# temperature_2.net
KiCad netlist of a schematic drawn in EAGLE
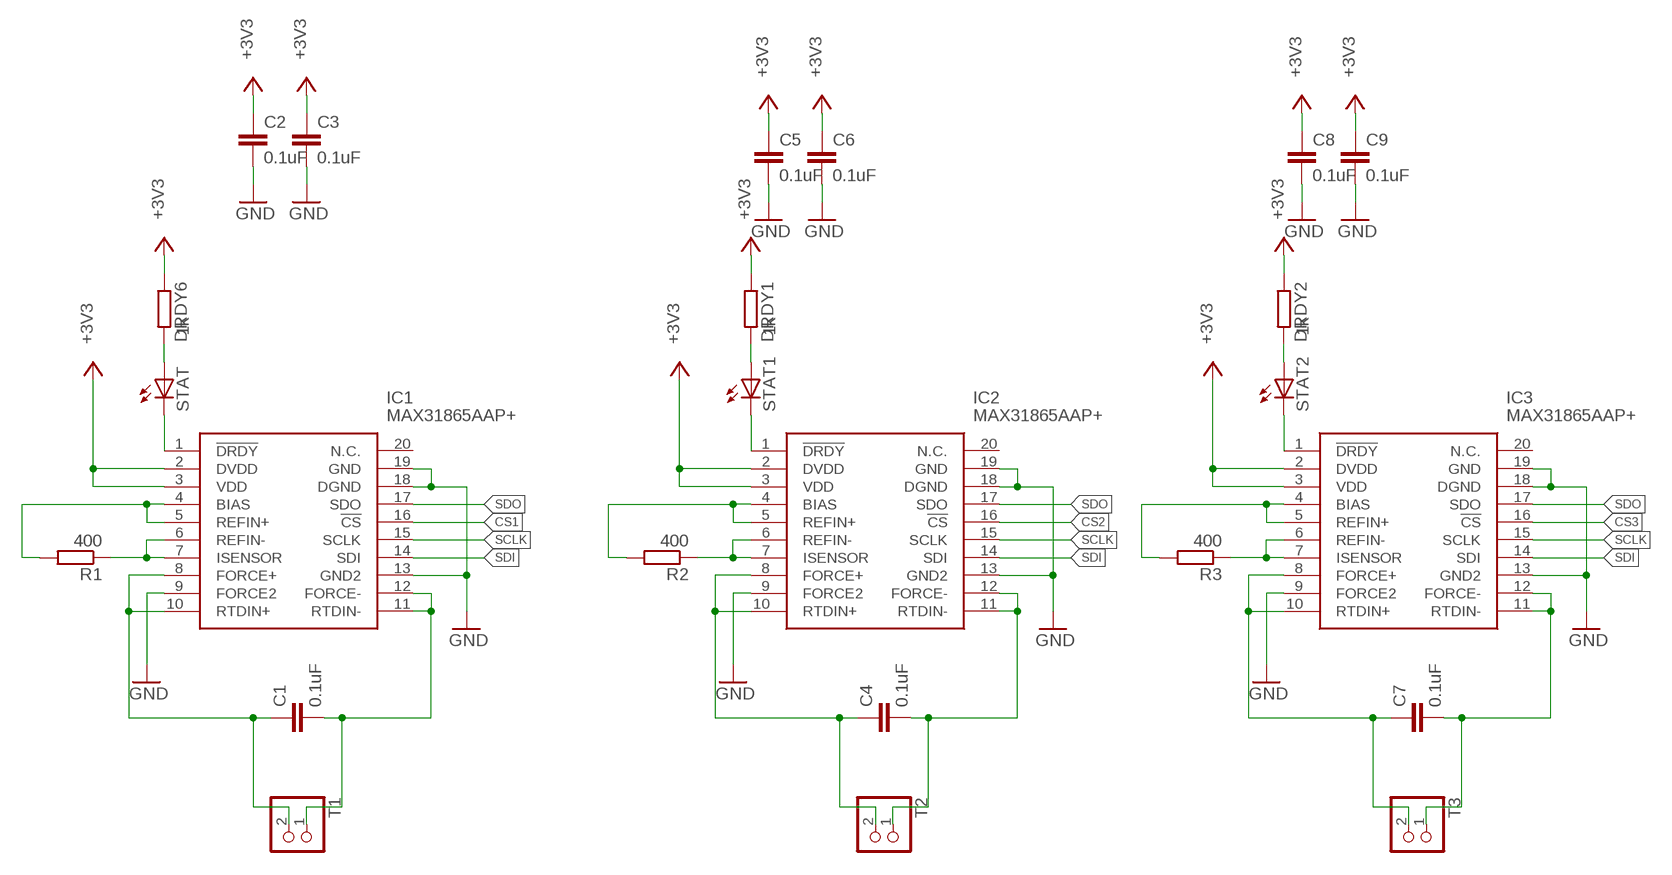
[diagram p0: schematic, sheet 1, part 1 of 2]
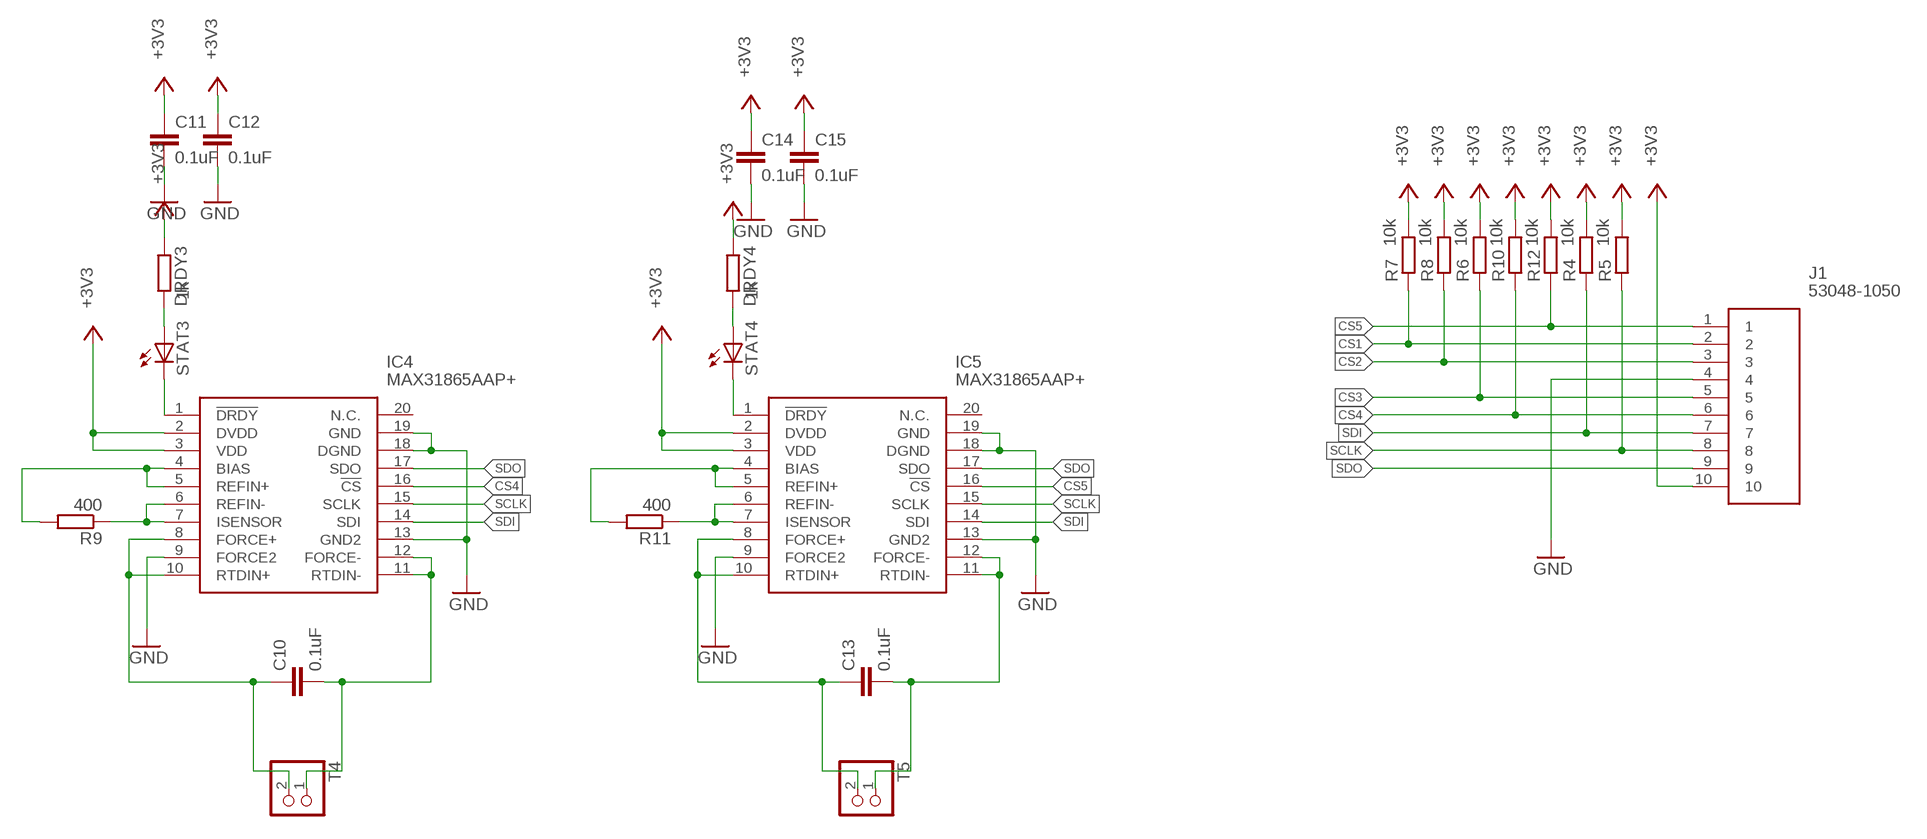
[diagram p1: schematic, sheet 1, part 2 of 2]

(export (version "E")
  (design (tool "Eeschema 10.0.6"))
  (components
    (comp (ref "C1")
      (value "0.1uF")
      (footprint "eagle-import:C0603K")
      (libsource (lib "eagle-import") (part "C-EUC0603K"))
    )
    (comp (ref "C2")
      (value "0.1uF")
      (footprint "eagle-import:C0603K")
      (libsource (lib "eagle-import") (part "C-EUC0603K"))
    )
    (comp (ref "C3")
      (value "0.1uF")
      (footprint "eagle-import:C0603K")
      (libsource (lib "eagle-import") (part "C-EUC0603K"))
    )
    (comp (ref "C4")
      (value "0.1uF")
      (footprint "eagle-import:C0603K")
      (libsource (lib "eagle-import") (part "C-EUC0603K"))
    )
    (comp (ref "C5")
      (value "0.1uF")
      (footprint "eagle-import:C0603K")
      (libsource (lib "eagle-import") (part "C-EUC0603K"))
    )
    (comp (ref "C6")
      (value "0.1uF")
      (footprint "eagle-import:C0603K")
      (libsource (lib "eagle-import") (part "C-EUC0603K"))
    )
    (comp (ref "C7")
      (value "0.1uF")
      (footprint "eagle-import:C0603K")
      (libsource (lib "eagle-import") (part "C-EUC0603K"))
    )
    (comp (ref "C8")
      (value "0.1uF")
      (footprint "eagle-import:C0603K")
      (libsource (lib "eagle-import") (part "C-EUC0603K"))
    )
    (comp (ref "C9")
      (value "0.1uF")
      (footprint "eagle-import:C0603K")
      (libsource (lib "eagle-import") (part "C-EUC0603K"))
    )
    (comp (ref "C10")
      (value "0.1uF")
      (footprint "eagle-import:C0603K")
      (libsource (lib "eagle-import") (part "C-EUC0603K"))
    )
    (comp (ref "C11")
      (value "0.1uF")
      (footprint "eagle-import:C0603K")
      (libsource (lib "eagle-import") (part "C-EUC0603K"))
    )
    (comp (ref "C12")
      (value "0.1uF")
      (footprint "eagle-import:C0603K")
      (libsource (lib "eagle-import") (part "C-EUC0603K"))
    )
    (comp (ref "C13")
      (value "0.1uF")
      (footprint "eagle-import:C0603K")
      (libsource (lib "eagle-import") (part "C-EUC0603K"))
    )
    (comp (ref "C14")
      (value "0.1uF")
      (footprint "eagle-import:C0603K")
      (libsource (lib "eagle-import") (part "C-EUC0603K"))
    )
    (comp (ref "C15")
      (value "0.1uF")
      (footprint "eagle-import:C0603K")
      (libsource (lib "eagle-import") (part "C-EUC0603K"))
    )
    (comp (ref "DRDY1")
      (value "1k")
      (footprint "eagle-import:R0603")
      (libsource (lib "eagle-import") (part "R-EU_R0603"))
    )
    (comp (ref "DRDY2")
      (value "1k")
      (footprint "eagle-import:R0603")
      (libsource (lib "eagle-import") (part "R-EU_R0603"))
    )
    (comp (ref "DRDY3")
      (value "1k")
      (footprint "eagle-import:R0603")
      (libsource (lib "eagle-import") (part "R-EU_R0603"))
    )
    (comp (ref "DRDY4")
      (value "1k")
      (footprint "eagle-import:R0603")
      (libsource (lib "eagle-import") (part "R-EU_R0603"))
    )
    (comp (ref "DRDY6")
      (value "1k")
      (footprint "eagle-import:R0603")
      (libsource (lib "eagle-import") (part "R-EU_R0603"))
    )
    (comp (ref "IC1")
      (value "MAX31865AAP+")
      (footprint "eagle-import:SOP65P778X199-20N")
      (fields
        (field (name "MOUSER_PART_NUMBER") "700-MAX31865AAP+")
        (field (name "RS_PART_NUMBER") "1901435")
      )
      (libsource (lib "eagle-import") (part "MAX31865AAP+"))
    )
    (comp (ref "IC2")
      (value "MAX31865AAP+")
      (footprint "eagle-import:SOP65P778X199-20N")
      (fields
        (field (name "MOUSER_PART_NUMBER") "700-MAX31865AAP+")
        (field (name "RS_PART_NUMBER") "1901435")
      )
      (libsource (lib "eagle-import") (part "MAX31865AAP+"))
    )
    (comp (ref "IC3")
      (value "MAX31865AAP+")
      (footprint "eagle-import:SOP65P778X199-20N")
      (fields
        (field (name "MOUSER_PART_NUMBER") "700-MAX31865AAP+")
        (field (name "RS_PART_NUMBER") "1901435")
      )
      (libsource (lib "eagle-import") (part "MAX31865AAP+"))
    )
    (comp (ref "IC4")
      (value "MAX31865AAP+")
      (footprint "eagle-import:SOP65P778X199-20N")
      (fields
        (field (name "MOUSER_PART_NUMBER") "700-MAX31865AAP+")
        (field (name "RS_PART_NUMBER") "1901435")
      )
      (libsource (lib "eagle-import") (part "MAX31865AAP+"))
    )
    (comp (ref "IC5")
      (value "MAX31865AAP+")
      (footprint "eagle-import:SOP65P778X199-20N")
      (fields
        (field (name "MOUSER_PART_NUMBER") "700-MAX31865AAP+")
        (field (name "RS_PART_NUMBER") "1901435")
      )
      (libsource (lib "eagle-import") (part "MAX31865AAP+"))
    )
    (comp (ref "J1")
      (value "53048-1050")
      (footprint "eagle-import:SHDRRA10W25P0X125_1X10_1425X55")
      (fields (field (name "MOUSER_PART_NUMBER") "538-53048-1050"))
      (libsource (lib "eagle-import") (part "53048-1050"))
    )
    (comp (ref "R1")
      (value "400")
      (footprint "eagle-import:R1206")
      (libsource (lib "eagle-import") (part "R-EU_R1206"))
    )
    (comp (ref "R2")
      (value "400")
      (footprint "eagle-import:R1206")
      (libsource (lib "eagle-import") (part "R-EU_R1206"))
    )
    (comp (ref "R3")
      (value "400")
      (footprint "eagle-import:R1206")
      (libsource (lib "eagle-import") (part "R-EU_R1206"))
    )
    (comp (ref "R4")
      (value "10k")
      (footprint "eagle-import:R0603")
      (libsource (lib "eagle-import") (part "R-EU_R0603"))
    )
    (comp (ref "R5")
      (value "10k")
      (footprint "eagle-import:R0603")
      (libsource (lib "eagle-import") (part "R-EU_R0603"))
    )
    (comp (ref "R6")
      (value "10k")
      (footprint "eagle-import:R0603")
      (libsource (lib "eagle-import") (part "R-EU_R0603"))
    )
    (comp (ref "R7")
      (value "10k")
      (footprint "eagle-import:R0603")
      (libsource (lib "eagle-import") (part "R-EU_R0603"))
    )
    (comp (ref "R8")
      (value "10k")
      (footprint "eagle-import:R0603")
      (libsource (lib "eagle-import") (part "R-EU_R0603"))
    )
    (comp (ref "R9")
      (value "400")
      (footprint "eagle-import:R1206")
      (libsource (lib "eagle-import") (part "R-EU_R1206"))
    )
    (comp (ref "R10")
      (value "10k")
      (footprint "eagle-import:R0603")
      (libsource (lib "eagle-import") (part "R-EU_R0603"))
    )
    (comp (ref "R11")
      (value "400")
      (footprint "eagle-import:R1206")
      (libsource (lib "eagle-import") (part "R-EU_R1206"))
    )
    (comp (ref "R12")
      (value "10k")
      (footprint "eagle-import:R0603")
      (libsource (lib "eagle-import") (part "R-EU_R0603"))
    )
    (comp (ref "STAT")
      (value "LEDCHIPLED_0805")
      (footprint "eagle-import:CHIPLED_0805")
      (libsource (lib "eagle-import") (part "LEDCHIPLED_0805"))
    )
    (comp (ref "STAT1")
      (value "LEDCHIPLED_0805")
      (footprint "eagle-import:CHIPLED_0805")
      (libsource (lib "eagle-import") (part "LEDCHIPLED_0805"))
    )
    (comp (ref "STAT2")
      (value "LEDCHIPLED_0805")
      (footprint "eagle-import:CHIPLED_0805")
      (libsource (lib "eagle-import") (part "LEDCHIPLED_0805"))
    )
    (comp (ref "STAT3")
      (value "LEDCHIPLED_0805")
      (footprint "eagle-import:CHIPLED_0805")
      (libsource (lib "eagle-import") (part "LEDCHIPLED_0805"))
    )
    (comp (ref "STAT4")
      (value "LEDCHIPLED_0805")
      (footprint "eagle-import:CHIPLED_0805")
      (libsource (lib "eagle-import") (part "LEDCHIPLED_0805"))
    )
    (comp (ref "T1")
      (value "PINHD-1X2")
      (footprint "eagle-import:1X02")
      (libsource (lib "eagle-import") (part "PINHD-1X2"))
    )
    (comp (ref "T2")
      (value "PINHD-1X2")
      (footprint "eagle-import:1X02")
      (libsource (lib "eagle-import") (part "PINHD-1X2"))
    )
    (comp (ref "T3")
      (value "PINHD-1X2")
      (footprint "eagle-import:1X02")
      (libsource (lib "eagle-import") (part "PINHD-1X2"))
    )
    (comp (ref "T4")
      (value "PINHD-1X2")
      (footprint "eagle-import:1X02")
      (libsource (lib "eagle-import") (part "PINHD-1X2"))
    )
    (comp (ref "T5")
      (value "PINHD-1X2")
      (footprint "eagle-import:1X02")
      (libsource (lib "eagle-import") (part "PINHD-1X2"))
    )
  )
  (nets
    (net (code "1") (name "+3V3") (class "Default")
      (node (ref "C11") (pin "1") (pinfunction "1_1") (pintype "passive"))
      (node (ref "C12") (pin "1") (pinfunction "1_1") (pintype "passive"))
      (node (ref "C14") (pin "1") (pinfunction "1_1") (pintype "passive"))
      (node (ref "C15") (pin "1") (pinfunction "1_1") (pintype "passive"))
      (node (ref "C2") (pin "1") (pinfunction "1_1") (pintype "passive"))
      (node (ref "C3") (pin "1") (pinfunction "1_1") (pintype "passive"))
      (node (ref "C5") (pin "1") (pinfunction "1_1") (pintype "passive"))
      (node (ref "C6") (pin "1") (pinfunction "1_1") (pintype "passive"))
      (node (ref "C8") (pin "1") (pinfunction "1_1") (pintype "passive"))
      (node (ref "C9") (pin "1") (pinfunction "1_1") (pintype "passive"))
      (node (ref "DRDY1") (pin "1") (pinfunction "1_1") (pintype "passive"))
      (node (ref "DRDY2") (pin "1") (pinfunction "1_1") (pintype "passive"))
      (node (ref "DRDY3") (pin "1") (pinfunction "1_1") (pintype "passive"))
      (node (ref "DRDY4") (pin "1") (pinfunction "1_1") (pintype "passive"))
      (node (ref "DRDY6") (pin "1") (pinfunction "1_1") (pintype "passive"))
      (node (ref "IC1") (pin "2") (pinfunction "DVDD_2") (pintype "power_in"))
      (node (ref "IC1") (pin "3") (pinfunction "VDD_3") (pintype "power_in"))
      (node (ref "IC2") (pin "2") (pinfunction "DVDD_2") (pintype "power_in"))
      (node (ref "IC2") (pin "3") (pinfunction "VDD_3") (pintype "power_in"))
      (node (ref "IC3") (pin "2") (pinfunction "DVDD_2") (pintype "power_in"))
      (node (ref "IC3") (pin "3") (pinfunction "VDD_3") (pintype "power_in"))
      (node (ref "IC4") (pin "2") (pinfunction "DVDD_2") (pintype "power_in"))
      (node (ref "IC4") (pin "3") (pinfunction "VDD_3") (pintype "power_in"))
      (node (ref "IC5") (pin "2") (pinfunction "DVDD_2") (pintype "power_in"))
      (node (ref "IC5") (pin "3") (pinfunction "VDD_3") (pintype "power_in"))
      (node (ref "J1") (pin "10") (pinfunction "10_10") (pintype "bidirectional"))
      (node (ref "R10") (pin "2") (pinfunction "2_2") (pintype "passive"))
      (node (ref "R12") (pin "2") (pinfunction "2_2") (pintype "passive"))
      (node (ref "R4") (pin "2") (pinfunction "2_2") (pintype "passive"))
      (node (ref "R5") (pin "2") (pinfunction "2_2") (pintype "passive"))
      (node (ref "R6") (pin "2") (pinfunction "2_2") (pintype "passive"))
      (node (ref "R7") (pin "2") (pinfunction "2_2") (pintype "passive"))
      (node (ref "R8") (pin "2") (pinfunction "2_2") (pintype "passive"))
    )
    (net (code "2") (name "CS1") (class "Default")
      (node (ref "IC1") (pin "16") (pinfunction "~{CS}_16") (pintype "input"))
      (node (ref "J1") (pin "2") (pinfunction "2_2") (pintype "bidirectional"))
      (node (ref "R7") (pin "1") (pinfunction "1_1") (pintype "passive"))
    )
    (net (code "3") (name "CS2") (class "Default")
      (node (ref "IC2") (pin "16") (pinfunction "~{CS}_16") (pintype "input"))
      (node (ref "J1") (pin "3") (pinfunction "3_3") (pintype "bidirectional"))
      (node (ref "R8") (pin "1") (pinfunction "1_1") (pintype "passive"))
    )
    (net (code "4") (name "CS3") (class "Default")
      (node (ref "IC3") (pin "16") (pinfunction "~{CS}_16") (pintype "input"))
      (node (ref "J1") (pin "5") (pinfunction "5_5") (pintype "bidirectional"))
      (node (ref "R6") (pin "1") (pinfunction "1_1") (pintype "passive"))
    )
    (net (code "5") (name "CS4") (class "Default")
      (node (ref "IC4") (pin "16") (pinfunction "~{CS}_16") (pintype "input"))
      (node (ref "J1") (pin "6") (pinfunction "6_6") (pintype "bidirectional"))
      (node (ref "R10") (pin "1") (pinfunction "1_1") (pintype "passive"))
    )
    (net (code "6") (name "CS5") (class "Default")
      (node (ref "IC5") (pin "16") (pinfunction "~{CS}_16") (pintype "input"))
      (node (ref "J1") (pin "1") (pinfunction "1_1") (pintype "bidirectional"))
      (node (ref "R12") (pin "1") (pinfunction "1_1") (pintype "passive"))
    )
    (net (code "7") (name "GND") (class "Default")
      (node (ref "C11") (pin "2") (pinfunction "2_2") (pintype "passive"))
      (node (ref "C12") (pin "2") (pinfunction "2_2") (pintype "passive"))
      (node (ref "C14") (pin "2") (pinfunction "2_2") (pintype "passive"))
      (node (ref "C15") (pin "2") (pinfunction "2_2") (pintype "passive"))
      (node (ref "C2") (pin "2") (pinfunction "2_2") (pintype "passive"))
      (node (ref "C3") (pin "2") (pinfunction "2_2") (pintype "passive"))
      (node (ref "C5") (pin "2") (pinfunction "2_2") (pintype "passive"))
      (node (ref "C6") (pin "2") (pinfunction "2_2") (pintype "passive"))
      (node (ref "C8") (pin "2") (pinfunction "2_2") (pintype "passive"))
      (node (ref "C9") (pin "2") (pinfunction "2_2") (pintype "passive"))
      (node (ref "IC1") (pin "13") (pinfunction "GND2_13") (pintype "power_in"))
      (node (ref "IC1") (pin "18") (pinfunction "DGND_18") (pintype "power_in"))
      (node (ref "IC1") (pin "19") (pinfunction "GND_19") (pintype "power_in"))
      (node (ref "IC1") (pin "9") (pinfunction "FORCE2_9") (pintype "bidirectional"))
      (node (ref "IC2") (pin "13") (pinfunction "GND2_13") (pintype "power_in"))
      (node (ref "IC2") (pin "18") (pinfunction "DGND_18") (pintype "power_in"))
      (node (ref "IC2") (pin "19") (pinfunction "GND_19") (pintype "power_in"))
      (node (ref "IC2") (pin "9") (pinfunction "FORCE2_9") (pintype "bidirectional"))
      (node (ref "IC3") (pin "13") (pinfunction "GND2_13") (pintype "power_in"))
      (node (ref "IC3") (pin "18") (pinfunction "DGND_18") (pintype "power_in"))
      (node (ref "IC3") (pin "19") (pinfunction "GND_19") (pintype "power_in"))
      (node (ref "IC3") (pin "9") (pinfunction "FORCE2_9") (pintype "bidirectional"))
      (node (ref "IC4") (pin "13") (pinfunction "GND2_13") (pintype "power_in"))
      (node (ref "IC4") (pin "18") (pinfunction "DGND_18") (pintype "power_in"))
      (node (ref "IC4") (pin "19") (pinfunction "GND_19") (pintype "power_in"))
      (node (ref "IC4") (pin "9") (pinfunction "FORCE2_9") (pintype "bidirectional"))
      (node (ref "IC5") (pin "13") (pinfunction "GND2_13") (pintype "power_in"))
      (node (ref "IC5") (pin "18") (pinfunction "DGND_18") (pintype "power_in"))
      (node (ref "IC5") (pin "19") (pinfunction "GND_19") (pintype "power_in"))
      (node (ref "IC5") (pin "9") (pinfunction "FORCE2_9") (pintype "bidirectional"))
      (node (ref "J1") (pin "4") (pinfunction "4_4") (pintype "bidirectional"))
    )
    (net (code "8") (name "Net-(DRDY1-Pad2)") (class "Default")
      (node (ref "DRDY1") (pin "2") (pinfunction "2_2") (pintype "passive"))
      (node (ref "STAT1") (pin "A") (pinfunction "A_A") (pintype "passive"))
    )
    (net (code "9") (name "Net-(DRDY2-Pad2)") (class "Default")
      (node (ref "DRDY2") (pin "2") (pinfunction "2_2") (pintype "passive"))
      (node (ref "STAT2") (pin "A") (pinfunction "A_A") (pintype "passive"))
    )
    (net (code "10") (name "Net-(DRDY3-Pad2)") (class "Default")
      (node (ref "DRDY3") (pin "2") (pinfunction "2_2") (pintype "passive"))
      (node (ref "STAT3") (pin "A") (pinfunction "A_A") (pintype "passive"))
    )
    (net (code "11") (name "Net-(DRDY4-Pad2)") (class "Default")
      (node (ref "DRDY4") (pin "2") (pinfunction "2_2") (pintype "passive"))
      (node (ref "STAT4") (pin "A") (pinfunction "A_A") (pintype "passive"))
    )
    (net (code "12") (name "Net-(DRDY6-Pad2)") (class "Default")
      (node (ref "DRDY6") (pin "2") (pinfunction "2_2") (pintype "passive"))
      (node (ref "STAT") (pin "A") (pinfunction "A_A") (pintype "passive"))
    )
    (net (code "13") (name "Net-(IC1-BIAS)") (class "Default")
      (node (ref "IC1") (pin "4") (pinfunction "BIAS_4") (pintype "output"))
      (node (ref "IC1") (pin "5") (pinfunction "REFIN+_5") (pintype "input"))
      (node (ref "R1") (pin "2") (pinfunction "2_2") (pintype "passive"))
    )
    (net (code "14") (name "Net-(IC1-FORCE+)") (class "Default")
      (node (ref "C1") (pin "1") (pinfunction "1_1") (pintype "passive"))
      (node (ref "IC1") (pin "10") (pinfunction "RTDIN+_10") (pintype "input"))
      (node (ref "IC1") (pin "8") (pinfunction "FORCE+_8") (pintype "bidirectional"))
      (node (ref "T1") (pin "2") (pinfunction "2_2") (pintype "passive"))
    )
    (net (code "15") (name "Net-(IC1-FORCE-)") (class "Default")
      (node (ref "C1") (pin "2") (pinfunction "2_2") (pintype "passive"))
      (node (ref "IC1") (pin "11") (pinfunction "RTDIN-_11") (pintype "input"))
      (node (ref "IC1") (pin "12") (pinfunction "FORCE-_12") (pintype "bidirectional"))
      (node (ref "T1") (pin "1") (pinfunction "1_1") (pintype "passive"))
    )
    (net (code "16") (name "Net-(IC1-ISENSOR)") (class "Default")
      (node (ref "IC1") (pin "6") (pinfunction "REFIN-_6") (pintype "input"))
      (node (ref "IC1") (pin "7") (pinfunction "ISENSOR_7") (pintype "bidirectional"))
      (node (ref "R1") (pin "1") (pinfunction "1_1") (pintype "passive"))
    )
    (net (code "17") (name "Net-(IC1-~{DRDY})") (class "Default")
      (node (ref "IC1") (pin "1") (pinfunction "~{DRDY}_1") (pintype "output"))
      (node (ref "STAT") (pin "C") (pinfunction "C_C") (pintype "passive"))
    )
    (net (code "18") (name "Net-(IC2-BIAS)") (class "Default")
      (node (ref "IC2") (pin "4") (pinfunction "BIAS_4") (pintype "output"))
      (node (ref "IC2") (pin "5") (pinfunction "REFIN+_5") (pintype "input"))
      (node (ref "R2") (pin "2") (pinfunction "2_2") (pintype "passive"))
    )
    (net (code "19") (name "Net-(IC2-FORCE+)") (class "Default")
      (node (ref "C4") (pin "1") (pinfunction "1_1") (pintype "passive"))
      (node (ref "IC2") (pin "10") (pinfunction "RTDIN+_10") (pintype "input"))
      (node (ref "IC2") (pin "8") (pinfunction "FORCE+_8") (pintype "bidirectional"))
      (node (ref "T2") (pin "2") (pinfunction "2_2") (pintype "passive"))
    )
    (net (code "20") (name "Net-(IC2-FORCE-)") (class "Default")
      (node (ref "C4") (pin "2") (pinfunction "2_2") (pintype "passive"))
      (node (ref "IC2") (pin "11") (pinfunction "RTDIN-_11") (pintype "input"))
      (node (ref "IC2") (pin "12") (pinfunction "FORCE-_12") (pintype "bidirectional"))
      (node (ref "T2") (pin "1") (pinfunction "1_1") (pintype "passive"))
    )
    (net (code "21") (name "Net-(IC2-ISENSOR)") (class "Default")
      (node (ref "IC2") (pin "6") (pinfunction "REFIN-_6") (pintype "input"))
      (node (ref "IC2") (pin "7") (pinfunction "ISENSOR_7") (pintype "bidirectional"))
      (node (ref "R2") (pin "1") (pinfunction "1_1") (pintype "passive"))
    )
    (net (code "22") (name "Net-(IC2-~{DRDY})") (class "Default")
      (node (ref "IC2") (pin "1") (pinfunction "~{DRDY}_1") (pintype "output"))
      (node (ref "STAT1") (pin "C") (pinfunction "C_C") (pintype "passive"))
    )
    (net (code "23") (name "Net-(IC3-BIAS)") (class "Default")
      (node (ref "IC3") (pin "4") (pinfunction "BIAS_4") (pintype "output"))
      (node (ref "IC3") (pin "5") (pinfunction "REFIN+_5") (pintype "input"))
      (node (ref "R3") (pin "2") (pinfunction "2_2") (pintype "passive"))
    )
    (net (code "24") (name "Net-(IC3-FORCE+)") (class "Default")
      (node (ref "C7") (pin "1") (pinfunction "1_1") (pintype "passive"))
      (node (ref "IC3") (pin "10") (pinfunction "RTDIN+_10") (pintype "input"))
      (node (ref "IC3") (pin "8") (pinfunction "FORCE+_8") (pintype "bidirectional"))
      (node (ref "T3") (pin "2") (pinfunction "2_2") (pintype "passive"))
    )
    (net (code "25") (name "Net-(IC3-FORCE-)") (class "Default")
      (node (ref "C7") (pin "2") (pinfunction "2_2") (pintype "passive"))
      (node (ref "IC3") (pin "11") (pinfunction "RTDIN-_11") (pintype "input"))
      (node (ref "IC3") (pin "12") (pinfunction "FORCE-_12") (pintype "bidirectional"))
      (node (ref "T3") (pin "1") (pinfunction "1_1") (pintype "passive"))
    )
    (net (code "26") (name "Net-(IC3-ISENSOR)") (class "Default")
      (node (ref "IC3") (pin "6") (pinfunction "REFIN-_6") (pintype "input"))
      (node (ref "IC3") (pin "7") (pinfunction "ISENSOR_7") (pintype "bidirectional"))
      (node (ref "R3") (pin "1") (pinfunction "1_1") (pintype "passive"))
    )
    (net (code "27") (name "Net-(IC3-~{DRDY})") (class "Default")
      (node (ref "IC3") (pin "1") (pinfunction "~{DRDY}_1") (pintype "output"))
      (node (ref "STAT2") (pin "C") (pinfunction "C_C") (pintype "passive"))
    )
    (net (code "28") (name "Net-(IC4-BIAS)") (class "Default")
      (node (ref "IC4") (pin "4") (pinfunction "BIAS_4") (pintype "output"))
      (node (ref "IC4") (pin "5") (pinfunction "REFIN+_5") (pintype "input"))
      (node (ref "R9") (pin "2") (pinfunction "2_2") (pintype "passive"))
    )
    (net (code "29") (name "Net-(IC4-FORCE+)") (class "Default")
      (node (ref "C10") (pin "1") (pinfunction "1_1") (pintype "passive"))
      (node (ref "IC4") (pin "10") (pinfunction "RTDIN+_10") (pintype "input"))
      (node (ref "IC4") (pin "8") (pinfunction "FORCE+_8") (pintype "bidirectional"))
      (node (ref "T4") (pin "2") (pinfunction "2_2") (pintype "passive"))
    )
    (net (code "30") (name "Net-(IC4-FORCE-)") (class "Default")
      (node (ref "C10") (pin "2") (pinfunction "2_2") (pintype "passive"))
      (node (ref "IC4") (pin "11") (pinfunction "RTDIN-_11") (pintype "input"))
      (node (ref "IC4") (pin "12") (pinfunction "FORCE-_12") (pintype "bidirectional"))
      (node (ref "T4") (pin "1") (pinfunction "1_1") (pintype "passive"))
    )
    (net (code "31") (name "Net-(IC4-ISENSOR)") (class "Default")
      (node (ref "IC4") (pin "6") (pinfunction "REFIN-_6") (pintype "input"))
      (node (ref "IC4") (pin "7") (pinfunction "ISENSOR_7") (pintype "bidirectional"))
      (node (ref "R9") (pin "1") (pinfunction "1_1") (pintype "passive"))
    )
    (net (code "32") (name "Net-(IC4-~{DRDY})") (class "Default")
      (node (ref "IC4") (pin "1") (pinfunction "~{DRDY}_1") (pintype "output"))
      (node (ref "STAT3") (pin "C") (pinfunction "C_C") (pintype "passive"))
    )
    (net (code "33") (name "Net-(IC5-BIAS)") (class "Default")
      (node (ref "IC5") (pin "4") (pinfunction "BIAS_4") (pintype "output"))
      (node (ref "IC5") (pin "5") (pinfunction "REFIN+_5") (pintype "input"))
      (node (ref "R11") (pin "2") (pinfunction "2_2") (pintype "passive"))
    )
    (net (code "34") (name "Net-(IC5-FORCE+)") (class "Default")
      (node (ref "C13") (pin "1") (pinfunction "1_1") (pintype "passive"))
      (node (ref "IC5") (pin "10") (pinfunction "RTDIN+_10") (pintype "input"))
      (node (ref "IC5") (pin "8") (pinfunction "FORCE+_8") (pintype "bidirectional"))
      (node (ref "T5") (pin "2") (pinfunction "2_2") (pintype "passive"))
    )
    (net (code "35") (name "Net-(IC5-FORCE-)") (class "Default")
      (node (ref "C13") (pin "2") (pinfunction "2_2") (pintype "passive"))
      (node (ref "IC5") (pin "11") (pinfunction "RTDIN-_11") (pintype "input"))
      (node (ref "IC5") (pin "12") (pinfunction "FORCE-_12") (pintype "bidirectional"))
      (node (ref "T5") (pin "1") (pinfunction "1_1") (pintype "passive"))
    )
    (net (code "36") (name "Net-(IC5-ISENSOR)") (class "Default")
      (node (ref "IC5") (pin "6") (pinfunction "REFIN-_6") (pintype "input"))
      (node (ref "IC5") (pin "7") (pinfunction "ISENSOR_7") (pintype "bidirectional"))
      (node (ref "R11") (pin "1") (pinfunction "1_1") (pintype "passive"))
    )
    (net (code "37") (name "Net-(IC5-~{DRDY})") (class "Default")
      (node (ref "IC5") (pin "1") (pinfunction "~{DRDY}_1") (pintype "output"))
      (node (ref "STAT4") (pin "C") (pinfunction "C_C") (pintype "passive"))
    )
    (net (code "38") (name "SCLK") (class "Default")
      (node (ref "IC1") (pin "15") (pinfunction "SCLK_15") (pintype "input"))
      (node (ref "IC2") (pin "15") (pinfunction "SCLK_15") (pintype "input"))
      (node (ref "IC3") (pin "15") (pinfunction "SCLK_15") (pintype "input"))
      (node (ref "IC4") (pin "15") (pinfunction "SCLK_15") (pintype "input"))
      (node (ref "IC5") (pin "15") (pinfunction "SCLK_15") (pintype "input"))
      (node (ref "J1") (pin "8") (pinfunction "8_8") (pintype "bidirectional"))
      (node (ref "R5") (pin "1") (pinfunction "1_1") (pintype "passive"))
    )
    (net (code "39") (name "SDI") (class "Default")
      (node (ref "IC1") (pin "14") (pinfunction "SDI_14") (pintype "input"))
      (node (ref "IC2") (pin "14") (pinfunction "SDI_14") (pintype "input"))
      (node (ref "IC3") (pin "14") (pinfunction "SDI_14") (pintype "input"))
      (node (ref "IC4") (pin "14") (pinfunction "SDI_14") (pintype "input"))
      (node (ref "IC5") (pin "14") (pinfunction "SDI_14") (pintype "input"))
      (node (ref "J1") (pin "7") (pinfunction "7_7") (pintype "bidirectional"))
      (node (ref "R4") (pin "1") (pinfunction "1_1") (pintype "passive"))
    )
    (net (code "40") (name "SDO") (class "Default")
      (node (ref "IC1") (pin "17") (pinfunction "SDO_17") (pintype "output"))
      (node (ref "IC2") (pin "17") (pinfunction "SDO_17") (pintype "output"))
      (node (ref "IC3") (pin "17") (pinfunction "SDO_17") (pintype "output"))
      (node (ref "IC4") (pin "17") (pinfunction "SDO_17") (pintype "output"))
      (node (ref "IC5") (pin "17") (pinfunction "SDO_17") (pintype "output"))
      (node (ref "J1") (pin "9") (pinfunction "9_9") (pintype "bidirectional"))
    )
    (net (code "41") (name "unconnected-(IC1-N.C.-Pad20)") (class "Default")
      (node (ref "IC1") (pin "20") (pinfunction "N.C._20") (pintype "no_connect"))
    )
    (net (code "42") (name "unconnected-(IC2-N.C.-Pad20)") (class "Default")
      (node (ref "IC2") (pin "20") (pinfunction "N.C._20") (pintype "no_connect"))
    )
    (net (code "43") (name "unconnected-(IC3-N.C.-Pad20)") (class "Default")
      (node (ref "IC3") (pin "20") (pinfunction "N.C._20") (pintype "no_connect"))
    )
    (net (code "44") (name "unconnected-(IC4-N.C.-Pad20)") (class "Default")
      (node (ref "IC4") (pin "20") (pinfunction "N.C._20") (pintype "no_connect"))
    )
    (net (code "45") (name "unconnected-(IC5-N.C.-Pad20)") (class "Default")
      (node (ref "IC5") (pin "20") (pinfunction "N.C._20") (pintype "no_connect"))
    )
  )
)
